# ioExpand.net
KiCad netlist of a schematic drawn in EAGLE
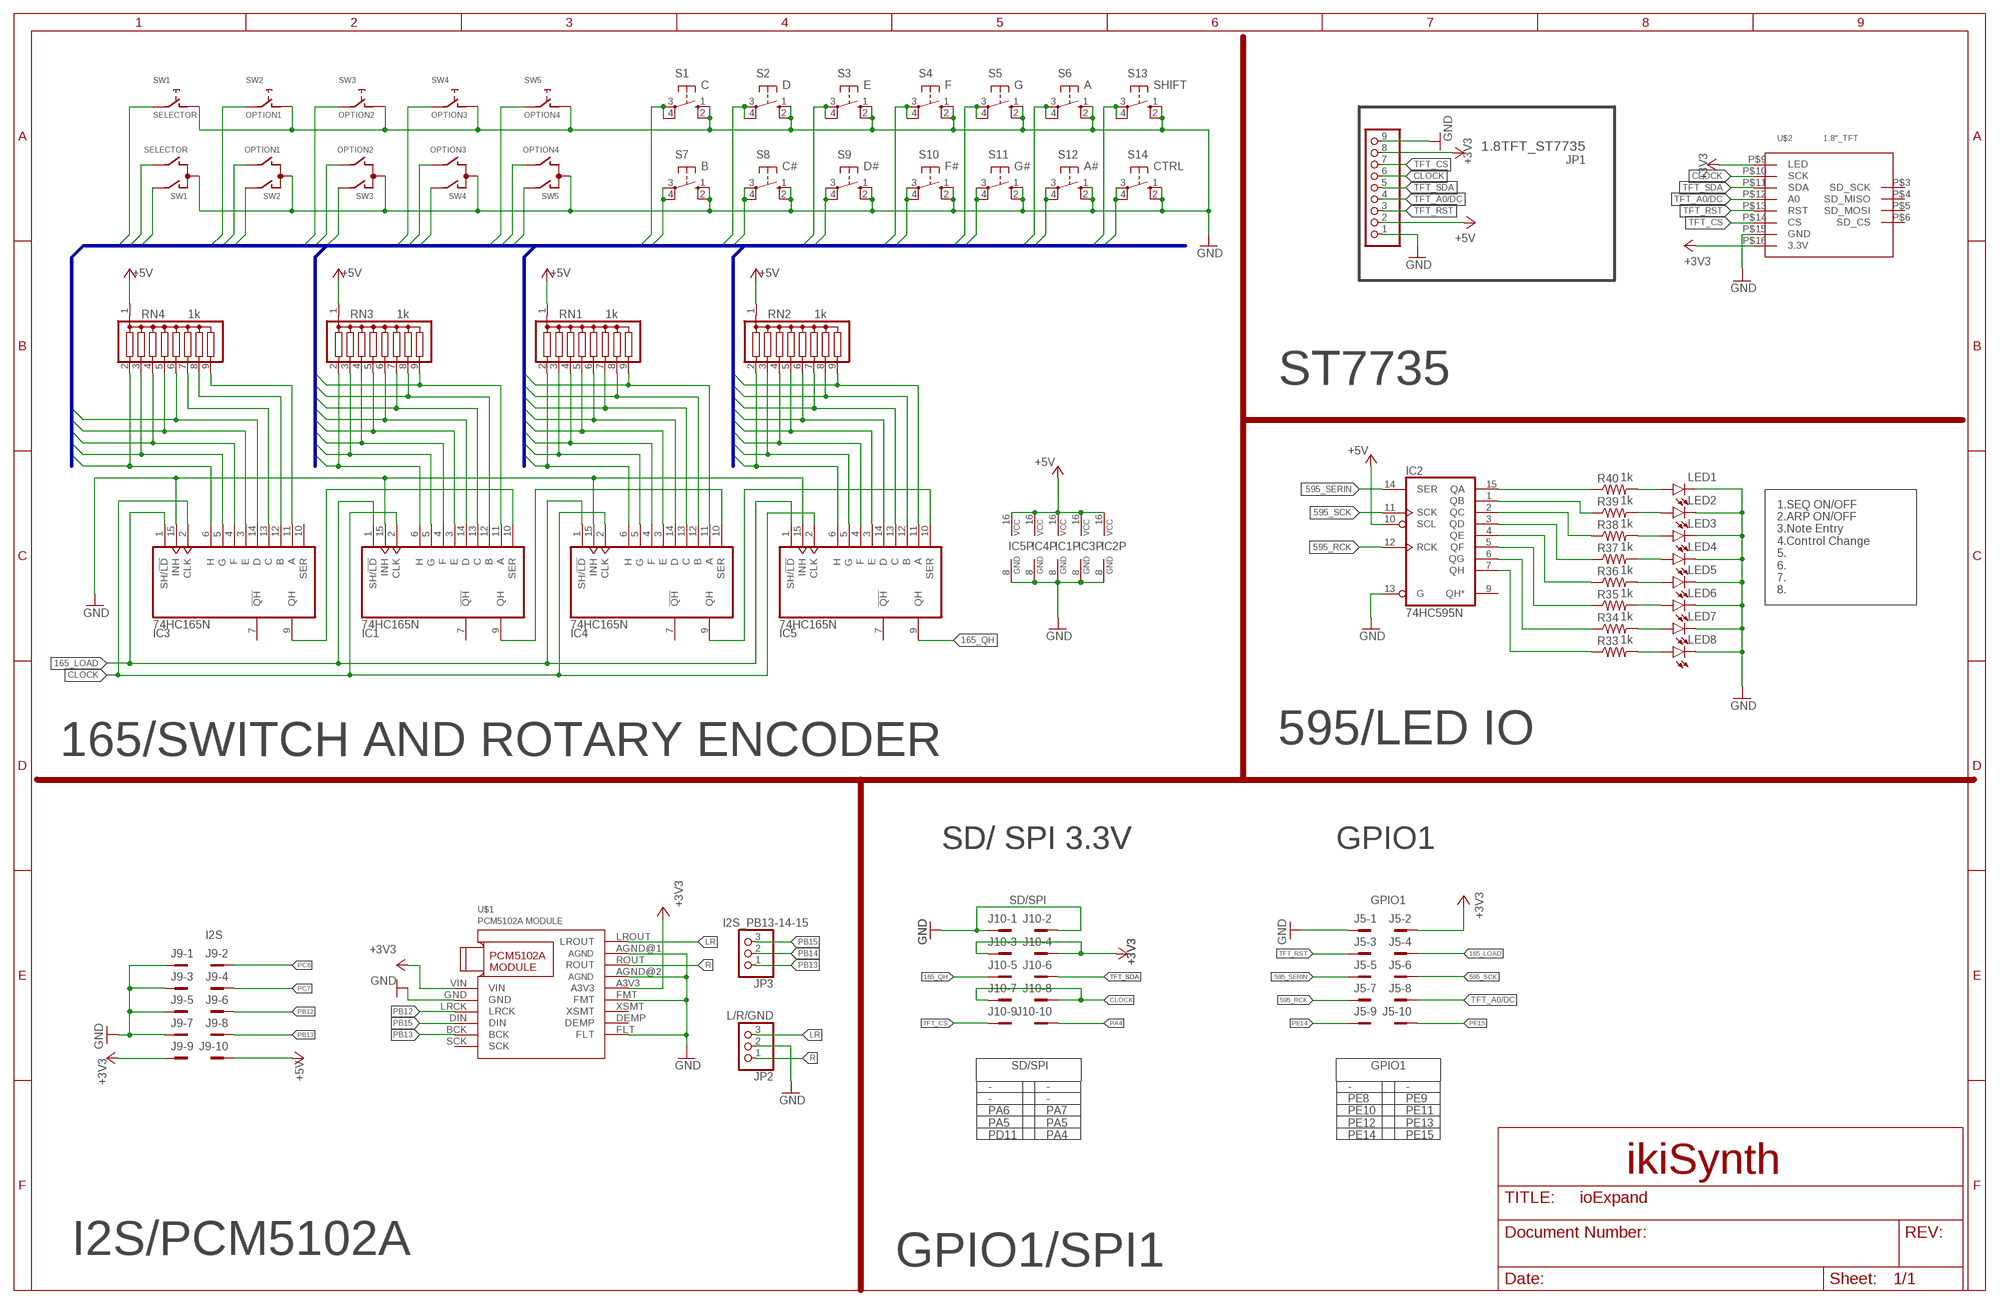
[diagram p0: schematic, sheet 1]

(export (version "E")
  (design (tool "Eeschema 10.0.6"))
  (components
    (comp (ref "IC1")
      (value "74HC165N")
      (footprint "eagle-import:DIL16")
      (libsource (lib "eagle-import") (part "74165NHC"))
    )
    (comp (ref "IC2")
      (value "74HC595N")
      (footprint "eagle-import:DIL16")
      (libsource (lib "eagle-import") (part "74595NHC"))
    )
    (comp (ref "IC3")
      (value "74HC165N")
      (footprint "eagle-import:DIL16")
      (libsource (lib "eagle-import") (part "74165NHC"))
    )
    (comp (ref "IC4")
      (value "74HC165N")
      (footprint "eagle-import:DIL16")
      (libsource (lib "eagle-import") (part "74165NHC"))
    )
    (comp (ref "IC5")
      (value "74HC165N")
      (footprint "eagle-import:DIL16")
      (libsource (lib "eagle-import") (part "74165NHC"))
    )
    (comp (ref "J5")
      (value "GPIO1")
      (footprint "eagle-import:PAK100_2500-10")
      (fields (field (name "MF") "3M") (field (name "MPN") "2510-6002UB"))
      (libsource (lib "eagle-import") (part "2510-"))
    )
    (comp (ref "J9")
      (value "I2S")
      (footprint "eagle-import:PAK100_2500-10")
      (fields (field (name "MF") "3M") (field (name "MPN") "2510-6002UB"))
      (libsource (lib "eagle-import") (part "2510-"))
    )
    (comp (ref "J10")
      (value "SD/SPI")
      (footprint "eagle-import:PAK100_2500-10")
      (fields (field (name "MF") "3M") (field (name "MPN") "2510-6002UB"))
      (libsource (lib "eagle-import") (part "2510-"))
    )
    (comp (ref "JP1")
      (value "1.8TFT_ST7735")
      (footprint "eagle-import:1X09")
      (libsource (lib "eagle-import") (part "PINHD-1X9"))
    )
    (comp (ref "JP2")
      (value "L/R/GND")
      (footprint "eagle-import:1X03")
      (libsource (lib "eagle-import") (part "PINHD-1X3"))
    )
    (comp (ref "JP3")
      (value "I2S_PB13-14-15")
      (footprint "eagle-import:1X03")
      (libsource (lib "eagle-import") (part "PINHD-1X3"))
    )
    (comp (ref "LED1")
      (value "LED3MM")
      (footprint "eagle-import:LED3MM")
      (libsource (lib "eagle-import") (part "LED3MM"))
    )
    (comp (ref "LED2")
      (value "LED3MM")
      (footprint "eagle-import:LED3MM")
      (libsource (lib "eagle-import") (part "LED3MM"))
    )
    (comp (ref "LED3")
      (value "LED3MM")
      (footprint "eagle-import:LED3MM")
      (libsource (lib "eagle-import") (part "LED3MM"))
    )
    (comp (ref "LED4")
      (value "LED3MM")
      (footprint "eagle-import:LED3MM")
      (libsource (lib "eagle-import") (part "LED3MM"))
    )
    (comp (ref "LED5")
      (value "LED3MM")
      (footprint "eagle-import:LED3MM")
      (libsource (lib "eagle-import") (part "LED3MM"))
    )
    (comp (ref "LED6")
      (value "LED3MM")
      (footprint "eagle-import:LED3MM")
      (libsource (lib "eagle-import") (part "LED3MM"))
    )
    (comp (ref "LED7")
      (value "LED3MM")
      (footprint "eagle-import:LED3MM")
      (libsource (lib "eagle-import") (part "LED3MM"))
    )
    (comp (ref "LED8")
      (value "LED3MM")
      (footprint "eagle-import:LED3MM")
      (libsource (lib "eagle-import") (part "LED3MM"))
    )
    (comp (ref "R33")
      (value "1k")
      (footprint "eagle-import:M1206")
      (libsource (lib "eagle-import") (part "R-US_M1206"))
    )
    (comp (ref "R34")
      (value "1k")
      (footprint "eagle-import:M1206")
      (libsource (lib "eagle-import") (part "R-US_M1206"))
    )
    (comp (ref "R35")
      (value "1k")
      (footprint "eagle-import:M1206")
      (libsource (lib "eagle-import") (part "R-US_M1206"))
    )
    (comp (ref "R36")
      (value "1k")
      (footprint "eagle-import:M1206")
      (libsource (lib "eagle-import") (part "R-US_M1206"))
    )
    (comp (ref "R37")
      (value "1k")
      (footprint "eagle-import:M1206")
      (libsource (lib "eagle-import") (part "R-US_M1206"))
    )
    (comp (ref "R38")
      (value "1k")
      (footprint "eagle-import:M1206")
      (libsource (lib "eagle-import") (part "R-US_M1206"))
    )
    (comp (ref "R39")
      (value "1k")
      (footprint "eagle-import:M1206")
      (libsource (lib "eagle-import") (part "R-US_M1206"))
    )
    (comp (ref "R40")
      (value "1k")
      (footprint "eagle-import:M1206")
      (libsource (lib "eagle-import") (part "R-US_M1206"))
    )
    (comp (ref "RN1")
      (value "1k")
      (footprint "eagle-import:SIL9")
      (libsource (lib "eagle-import") (part "G08R"))
    )
    (comp (ref "RN2")
      (value "1k")
      (footprint "eagle-import:SIL9")
      (libsource (lib "eagle-import") (part "G08R"))
    )
    (comp (ref "RN3")
      (value "1k")
      (footprint "eagle-import:SIL9")
      (libsource (lib "eagle-import") (part "G08R"))
    )
    (comp (ref "RN4")
      (value "1k")
      (footprint "eagle-import:SIL9")
      (libsource (lib "eagle-import") (part "G08R"))
    )
    (comp (ref "S1")
      (value "C")
      (footprint "eagle-import:B3F-40XX")
      (fields (field (name "MF") "OMRON COMPONENTS USA") (field (name "MPN") "B3F-4000"))
      (libsource (lib "eagle-import") (part "40-XX"))
    )
    (comp (ref "S2")
      (value "D")
      (footprint "eagle-import:B3F-40XX")
      (fields (field (name "MF") "OMRON COMPONENTS USA") (field (name "MPN") "B3F-4000"))
      (libsource (lib "eagle-import") (part "40-XX"))
    )
    (comp (ref "S3")
      (value "E")
      (footprint "eagle-import:B3F-40XX")
      (fields (field (name "MF") "OMRON COMPONENTS USA") (field (name "MPN") "B3F-4000"))
      (libsource (lib "eagle-import") (part "40-XX"))
    )
    (comp (ref "S4")
      (value "F")
      (footprint "eagle-import:B3F-40XX")
      (fields (field (name "MF") "OMRON COMPONENTS USA") (field (name "MPN") "B3F-4000"))
      (libsource (lib "eagle-import") (part "40-XX"))
    )
    (comp (ref "S5")
      (value "G")
      (footprint "eagle-import:B3F-40XX")
      (fields (field (name "MF") "OMRON COMPONENTS USA") (field (name "MPN") "B3F-4000"))
      (libsource (lib "eagle-import") (part "40-XX"))
    )
    (comp (ref "S6")
      (value "A")
      (footprint "eagle-import:B3F-40XX")
      (fields (field (name "MF") "OMRON COMPONENTS USA") (field (name "MPN") "B3F-4000"))
      (libsource (lib "eagle-import") (part "40-XX"))
    )
    (comp (ref "S7")
      (value "B")
      (footprint "eagle-import:B3F-40XX")
      (fields (field (name "MF") "OMRON COMPONENTS USA") (field (name "MPN") "B3F-4000"))
      (libsource (lib "eagle-import") (part "40-XX"))
    )
    (comp (ref "S8")
      (value "C#")
      (footprint "eagle-import:B3F-40XX")
      (fields (field (name "MF") "OMRON COMPONENTS USA") (field (name "MPN") "B3F-4000"))
      (libsource (lib "eagle-import") (part "40-XX"))
    )
    (comp (ref "S9")
      (value "D#")
      (footprint "eagle-import:B3F-40XX")
      (fields (field (name "MF") "OMRON COMPONENTS USA") (field (name "MPN") "B3F-4000"))
      (libsource (lib "eagle-import") (part "40-XX"))
    )
    (comp (ref "S10")
      (value "F#")
      (footprint "eagle-import:B3F-40XX")
      (fields (field (name "MF") "OMRON COMPONENTS USA") (field (name "MPN") "B3F-4000"))
      (libsource (lib "eagle-import") (part "40-XX"))
    )
    (comp (ref "S11")
      (value "G#")
      (footprint "eagle-import:B3F-40XX")
      (fields (field (name "MF") "OMRON COMPONENTS USA") (field (name "MPN") "B3F-4000"))
      (libsource (lib "eagle-import") (part "40-XX"))
    )
    (comp (ref "S12")
      (value "A#")
      (footprint "eagle-import:B3F-40XX")
      (fields (field (name "MF") "OMRON COMPONENTS USA") (field (name "MPN") "B3F-4000"))
      (libsource (lib "eagle-import") (part "40-XX"))
    )
    (comp (ref "S13")
      (value "SHIFT")
      (footprint "eagle-import:B3F-40XX")
      (fields (field (name "MF") "OMRON COMPONENTS USA") (field (name "MPN") "B3F-4000"))
      (libsource (lib "eagle-import") (part "40-XX"))
    )
    (comp (ref "S14")
      (value "CTRL")
      (footprint "eagle-import:B3F-40XX")
      (fields (field (name "MF") "OMRON COMPONENTS USA") (field (name "MPN") "B3F-4000"))
      (libsource (lib "eagle-import") (part "40-XX"))
    )
    (comp (ref "SW1")
      (value "SELECTOR")
      (footprint "eagle-import:ALPS_EC12E_SW")
      (fields (field (name "MPN") "EC12E2424407"))
      (libsource (lib "eagle-import") (part "EC12E_SW"))
    )
    (comp (ref "SW2")
      (value "OPTION1")
      (footprint "eagle-import:ALPS_EC12E_SW")
      (fields (field (name "MPN") "EC12E2424407"))
      (libsource (lib "eagle-import") (part "EC12E_SW"))
    )
    (comp (ref "SW3")
      (value "OPTION2")
      (footprint "eagle-import:ALPS_EC12E_SW")
      (fields (field (name "MPN") "EC12E2424407"))
      (libsource (lib "eagle-import") (part "EC12E_SW"))
    )
    (comp (ref "SW4")
      (value "OPTION3")
      (footprint "eagle-import:ALPS_EC12E_SW")
      (fields (field (name "MPN") "EC12E2424407"))
      (libsource (lib "eagle-import") (part "EC12E_SW"))
    )
    (comp (ref "SW5")
      (value "OPTION4")
      (footprint "eagle-import:ALPS_EC12E_SW")
      (fields (field (name "MPN") "EC12E2424407"))
      (libsource (lib "eagle-import") (part "EC12E_SW"))
    )
    (comp (ref "U$1")
      (value "PCM5102A_MODULE")
      (footprint "eagle-import:PCM5102A_MODULE")
      (libsource (lib "eagle-import") (part "PCM5102A_MODULE"))
    )
    (comp (ref "U$2")
      (value "1.8\"_TFT")
      (footprint "eagle-import:1.8__TFT")
      (libsource (lib "eagle-import") (part "1.8{dblquote}_TFT"))
    )
  )
  (nets
    (net (code "1") (name "+3V3") (class "Default")
      (node (ref "J10") (pin "3") (pinfunction "KL_3") (pintype "passive"))
      (node (ref "J10") (pin "4") (pinfunction "KL_4") (pintype "passive"))
      (node (ref "J5") (pin "2") (pinfunction "KL_2") (pintype "passive"))
      (node (ref "J9") (pin "9") (pinfunction "KL_9") (pintype "passive"))
      (node (ref "JP1") (pin "8") (pinfunction "8_8") (pintype "passive"))
      (node (ref "U$1") (pin "A3V3") (pinfunction "A3V3_A3V3") (pintype "power_in"))
      (node (ref "U$1") (pin "VIN") (pinfunction "VIN_VIN") (pintype "power_in"))
      (node (ref "U$2") (pin "P$16") (pinfunction "3.3V_P$16") (pintype "bidirectional"))
      (node (ref "U$2") (pin "P$9") (pinfunction "LED_P$9") (pintype "bidirectional"))
    )
    (net (code "2") (name "+5V") (class "Default")
      (node (ref "IC1") (pin "16") (pinfunction "VCC_16") (pintype "power_in"))
      (node (ref "IC2") (pin "10") (pinfunction "SCL_10") (pintype "input"))
      (node (ref "IC2") (pin "16") (pinfunction "VCC_16") (pintype "power_in"))
      (node (ref "IC3") (pin "16") (pinfunction "VCC_16") (pintype "power_in"))
      (node (ref "IC4") (pin "16") (pinfunction "VCC_16") (pintype "power_in"))
      (node (ref "IC5") (pin "16") (pinfunction "VCC_16") (pintype "power_in"))
      (node (ref "J9") (pin "10") (pinfunction "KL_10") (pintype "passive"))
      (node (ref "JP1") (pin "2") (pinfunction "2_2") (pintype "passive"))
      (node (ref "RN1") (pin "1") (pinfunction "1_1") (pintype "passive"))
      (node (ref "RN2") (pin "1") (pinfunction "1_1") (pintype "passive"))
      (node (ref "RN3") (pin "1") (pinfunction "1_1") (pintype "passive"))
      (node (ref "RN4") (pin "1") (pinfunction "1_1") (pintype "passive"))
    )
    (net (code "3") (name "/CTRL") (class "Default")
      (node (ref "IC3") (pin "3") (pinfunction "E_3") (pintype "input"))
      (node (ref "RN4") (pin "5") (pinfunction "5_5") (pintype "passive"))
      (node (ref "S14") (pin "3") (pinfunction "P_3") (pintype "passive"))
      (node (ref "S14") (pin "4") (pinfunction "P1_4") (pintype "passive"))
    )
    (net (code "4") (name "/KEY1") (class "Default")
      (node (ref "IC1") (pin "11") (pinfunction "A_11") (pintype "input"))
      (node (ref "RN3") (pin "9") (pinfunction "9_9") (pintype "passive"))
      (node (ref "S1") (pin "3") (pinfunction "P_3") (pintype "passive"))
      (node (ref "S1") (pin "4") (pinfunction "P1_4") (pintype "passive"))
    )
    (net (code "5") (name "/KEY2") (class "Default")
      (node (ref "IC1") (pin "13") (pinfunction "C_13") (pintype "input"))
      (node (ref "RN3") (pin "7") (pinfunction "7_7") (pintype "passive"))
      (node (ref "S2") (pin "3") (pinfunction "P_3") (pintype "passive"))
      (node (ref "S2") (pin "4") (pinfunction "P1_4") (pintype "passive"))
    )
    (net (code "6") (name "/KEY3") (class "Default")
      (node (ref "IC1") (pin "3") (pinfunction "E_3") (pintype "input"))
      (node (ref "RN3") (pin "5") (pinfunction "5_5") (pintype "passive"))
      (node (ref "S3") (pin "3") (pinfunction "P_3") (pintype "passive"))
      (node (ref "S3") (pin "4") (pinfunction "P1_4") (pintype "passive"))
    )
    (net (code "7") (name "/KEY4") (class "Default")
      (node (ref "IC1") (pin "4") (pinfunction "F_4") (pintype "input"))
      (node (ref "RN3") (pin "4") (pinfunction "4_4") (pintype "passive"))
      (node (ref "S4") (pin "3") (pinfunction "P_3") (pintype "passive"))
      (node (ref "S4") (pin "4") (pinfunction "P1_4") (pintype "passive"))
    )
    (net (code "8") (name "/KEY5") (class "Default")
      (node (ref "IC4") (pin "11") (pinfunction "A_11") (pintype "input"))
      (node (ref "RN1") (pin "9") (pinfunction "9_9") (pintype "passive"))
      (node (ref "S5") (pin "3") (pinfunction "P_3") (pintype "passive"))
      (node (ref "S5") (pin "4") (pinfunction "P1_4") (pintype "passive"))
    )
    (net (code "9") (name "/KEY6") (class "Default")
      (node (ref "IC4") (pin "12") (pinfunction "B_12") (pintype "input"))
      (node (ref "RN1") (pin "8") (pinfunction "8_8") (pintype "passive"))
      (node (ref "S6") (pin "3") (pinfunction "P_3") (pintype "passive"))
      (node (ref "S6") (pin "4") (pinfunction "P1_4") (pintype "passive"))
    )
    (net (code "10") (name "/KEY7") (class "Default")
      (node (ref "IC4") (pin "14") (pinfunction "D_14") (pintype "input"))
      (node (ref "RN1") (pin "6") (pinfunction "6_6") (pintype "passive"))
      (node (ref "S7") (pin "3") (pinfunction "P_3") (pintype "passive"))
      (node (ref "S7") (pin "4") (pinfunction "P1_4") (pintype "passive"))
    )
    (net (code "11") (name "/KEY8") (class "Default")
      (node (ref "IC1") (pin "12") (pinfunction "B_12") (pintype "input"))
      (node (ref "RN3") (pin "8") (pinfunction "8_8") (pintype "passive"))
      (node (ref "S8") (pin "3") (pinfunction "P_3") (pintype "passive"))
      (node (ref "S8") (pin "4") (pinfunction "P1_4") (pintype "passive"))
    )
    (net (code "12") (name "/KEY9") (class "Default")
      (node (ref "IC1") (pin "14") (pinfunction "D_14") (pintype "input"))
      (node (ref "RN3") (pin "6") (pinfunction "6_6") (pintype "passive"))
      (node (ref "S9") (pin "3") (pinfunction "P_3") (pintype "passive"))
      (node (ref "S9") (pin "4") (pinfunction "P1_4") (pintype "passive"))
    )
    (net (code "13") (name "/KEY10") (class "Default")
      (node (ref "IC1") (pin "5") (pinfunction "G_5") (pintype "input"))
      (node (ref "RN3") (pin "3") (pinfunction "3_3") (pintype "passive"))
      (node (ref "S10") (pin "3") (pinfunction "P_3") (pintype "passive"))
      (node (ref "S10") (pin "4") (pinfunction "P1_4") (pintype "passive"))
    )
    (net (code "14") (name "/KEY11") (class "Default")
      (node (ref "IC1") (pin "6") (pinfunction "H_6") (pintype "input"))
      (node (ref "RN3") (pin "2") (pinfunction "2_2") (pintype "passive"))
      (node (ref "S11") (pin "3") (pinfunction "P_3") (pintype "passive"))
      (node (ref "S11") (pin "4") (pinfunction "P1_4") (pintype "passive"))
    )
    (net (code "15") (name "/KEY12") (class "Default")
      (node (ref "IC4") (pin "13") (pinfunction "C_13") (pintype "input"))
      (node (ref "RN1") (pin "7") (pinfunction "7_7") (pintype "passive"))
      (node (ref "S12") (pin "3") (pinfunction "P_3") (pintype "passive"))
      (node (ref "S12") (pin "4") (pinfunction "P1_4") (pintype "passive"))
    )
    (net (code "16") (name "/ROTSW1") (class "Default")
      (node (ref "IC3") (pin "6") (pinfunction "H_6") (pintype "input"))
      (node (ref "RN4") (pin "2") (pinfunction "2_2") (pintype "passive"))
      (node (ref "SW1") (pin "E") (pinfunction "2_E") (pintype "passive"))
    )
    (net (code "17") (name "/ROTSW2") (class "Default")
      (node (ref "IC5") (pin "6") (pinfunction "H_6") (pintype "input"))
      (node (ref "RN2") (pin "2") (pinfunction "2_2") (pintype "passive"))
      (node (ref "SW2") (pin "E") (pinfunction "2_E") (pintype "passive"))
    )
    (net (code "18") (name "/ROTSW3") (class "Default")
      (node (ref "IC5") (pin "3") (pinfunction "E_3") (pintype "input"))
      (node (ref "RN2") (pin "5") (pinfunction "5_5") (pintype "passive"))
      (node (ref "SW3") (pin "E") (pinfunction "2_E") (pintype "passive"))
    )
    (net (code "19") (name "/ROTSW4") (class "Default")
      (node (ref "IC5") (pin "12") (pinfunction "B_12") (pintype "input"))
      (node (ref "RN2") (pin "8") (pinfunction "8_8") (pintype "passive"))
      (node (ref "SW4") (pin "E") (pinfunction "2_E") (pintype "passive"))
    )
    (net (code "20") (name "/ROTSW5") (class "Default")
      (node (ref "IC4") (pin "5") (pinfunction "G_5") (pintype "input"))
      (node (ref "RN1") (pin "3") (pinfunction "3_3") (pintype "passive"))
      (node (ref "SW5") (pin "E") (pinfunction "2_E") (pintype "passive"))
    )
    (net (code "21") (name "/ROTSW_AB1") (class "Default")
      (node (ref "IC3") (pin "5") (pinfunction "G_5") (pintype "input"))
      (node (ref "RN4") (pin "3") (pinfunction "3_3") (pintype "passive"))
      (node (ref "SW1") (pin "B") (pinfunction "B_B") (pintype "passive"))
    )
    (net (code "22") (name "/ROTSW_AB2") (class "Default")
      (node (ref "IC3") (pin "4") (pinfunction "F_4") (pintype "input"))
      (node (ref "RN4") (pin "4") (pinfunction "4_4") (pintype "passive"))
      (node (ref "SW1") (pin "A") (pinfunction "A_A") (pintype "passive"))
    )
    (net (code "23") (name "/ROTSW_AB3") (class "Default")
      (node (ref "IC5") (pin "5") (pinfunction "G_5") (pintype "input"))
      (node (ref "RN2") (pin "3") (pinfunction "3_3") (pintype "passive"))
      (node (ref "SW2") (pin "B") (pinfunction "B_B") (pintype "passive"))
    )
    (net (code "24") (name "/ROTSW_AB4") (class "Default")
      (node (ref "IC5") (pin "4") (pinfunction "F_4") (pintype "input"))
      (node (ref "RN2") (pin "4") (pinfunction "4_4") (pintype "passive"))
      (node (ref "SW2") (pin "A") (pinfunction "A_A") (pintype "passive"))
    )
    (net (code "25") (name "/ROTSW_AB5") (class "Default")
      (node (ref "IC5") (pin "14") (pinfunction "D_14") (pintype "input"))
      (node (ref "RN2") (pin "6") (pinfunction "6_6") (pintype "passive"))
      (node (ref "SW3") (pin "B") (pinfunction "B_B") (pintype "passive"))
    )
    (net (code "26") (name "/ROTSW_AB6") (class "Default")
      (node (ref "IC5") (pin "13") (pinfunction "C_13") (pintype "input"))
      (node (ref "RN2") (pin "7") (pinfunction "7_7") (pintype "passive"))
      (node (ref "SW3") (pin "A") (pinfunction "A_A") (pintype "passive"))
    )
    (net (code "27") (name "/ROTSW_AB7") (class "Default")
      (node (ref "IC5") (pin "11") (pinfunction "A_11") (pintype "input"))
      (node (ref "RN2") (pin "9") (pinfunction "9_9") (pintype "passive"))
      (node (ref "SW4") (pin "B") (pinfunction "B_B") (pintype "passive"))
    )
    (net (code "28") (name "/ROTSW_AB8") (class "Default")
      (node (ref "IC4") (pin "6") (pinfunction "H_6") (pintype "input"))
      (node (ref "RN1") (pin "2") (pinfunction "2_2") (pintype "passive"))
      (node (ref "SW4") (pin "A") (pinfunction "A_A") (pintype "passive"))
    )
    (net (code "29") (name "/ROTSW_AB9") (class "Default")
      (node (ref "IC4") (pin "4") (pinfunction "F_4") (pintype "input"))
      (node (ref "RN1") (pin "4") (pinfunction "4_4") (pintype "passive"))
      (node (ref "SW5") (pin "B") (pinfunction "B_B") (pintype "passive"))
    )
    (net (code "30") (name "/ROTSW_AB10") (class "Default")
      (node (ref "IC4") (pin "3") (pinfunction "E_3") (pintype "input"))
      (node (ref "RN1") (pin "5") (pinfunction "5_5") (pintype "passive"))
      (node (ref "SW5") (pin "A") (pinfunction "A_A") (pintype "passive"))
    )
    (net (code "31") (name "/SHIFT") (class "Default")
      (node (ref "IC3") (pin "14") (pinfunction "D_14") (pintype "input"))
      (node (ref "RN4") (pin "6") (pinfunction "6_6") (pintype "passive"))
      (node (ref "S13") (pin "3") (pinfunction "P_3") (pintype "passive"))
      (node (ref "S13") (pin "4") (pinfunction "P1_4") (pintype "passive"))
    )
    (net (code "32") (name "165_LOAD") (class "Default")
      (node (ref "IC1") (pin "1") (pinfunction "SH/~{LD}_1") (pintype "input"))
      (node (ref "IC3") (pin "1") (pinfunction "SH/~{LD}_1") (pintype "input"))
      (node (ref "IC4") (pin "1") (pinfunction "SH/~{LD}_1") (pintype "input"))
      (node (ref "IC5") (pin "1") (pinfunction "SH/~{LD}_1") (pintype "input"))
      (node (ref "J5") (pin "4") (pinfunction "KL_4") (pintype "passive"))
    )
    (net (code "33") (name "165_QH") (class "Default")
      (node (ref "IC5") (pin "9") (pinfunction "QH_9") (pintype "output"))
      (node (ref "J10") (pin "5") (pinfunction "KL_5") (pintype "passive"))
    )
    (net (code "34") (name "595_RCK") (class "Default")
      (node (ref "IC2") (pin "12") (pinfunction "RCK_12") (pintype "input"))
      (node (ref "J5") (pin "7") (pinfunction "KL_7") (pintype "passive"))
    )
    (net (code "35") (name "595_SCK") (class "Default")
      (node (ref "IC2") (pin "11") (pinfunction "SCK_11") (pintype "input"))
      (node (ref "J5") (pin "6") (pinfunction "KL_6") (pintype "passive"))
    )
    (net (code "36") (name "595_SERIN") (class "Default")
      (node (ref "IC2") (pin "14") (pinfunction "SER_14") (pintype "input"))
      (node (ref "J5") (pin "5") (pinfunction "KL_5") (pintype "passive"))
    )
    (net (code "37") (name "CLOCK") (class "Default")
      (node (ref "IC1") (pin "2") (pinfunction "CLK_2") (pintype "input"))
      (node (ref "IC3") (pin "2") (pinfunction "CLK_2") (pintype "input"))
      (node (ref "IC4") (pin "2") (pinfunction "CLK_2") (pintype "input"))
      (node (ref "IC5") (pin "2") (pinfunction "CLK_2") (pintype "input"))
      (node (ref "J10") (pin "7") (pinfunction "KL_7") (pintype "passive"))
      (node (ref "J10") (pin "8") (pinfunction "KL_8") (pintype "passive"))
      (node (ref "JP1") (pin "6") (pinfunction "6_6") (pintype "passive"))
      (node (ref "U$2") (pin "P$10") (pinfunction "SCK_P$10") (pintype "bidirectional"))
    )
    (net (code "38") (name "GND") (class "Default")
      (node (ref "IC1") (pin "15") (pinfunction "INH_15") (pintype "input"))
      (node (ref "IC1") (pin "8") (pinfunction "GND_8") (pintype "power_in"))
      (node (ref "IC2") (pin "13") (pinfunction "G_13") (pintype "input"))
      (node (ref "IC2") (pin "8") (pinfunction "GND_8") (pintype "power_in"))
      (node (ref "IC3") (pin "15") (pinfunction "INH_15") (pintype "input"))
      (node (ref "IC3") (pin "8") (pinfunction "GND_8") (pintype "power_in"))
      (node (ref "IC4") (pin "15") (pinfunction "INH_15") (pintype "input"))
      (node (ref "IC4") (pin "8") (pinfunction "GND_8") (pintype "power_in"))
      (node (ref "IC5") (pin "15") (pinfunction "INH_15") (pintype "input"))
      (node (ref "IC5") (pin "8") (pinfunction "GND_8") (pintype "power_in"))
      (node (ref "J10") (pin "1") (pinfunction "KL_1") (pintype "passive"))
      (node (ref "J10") (pin "2") (pinfunction "KL_2") (pintype "passive"))
      (node (ref "J5") (pin "1") (pinfunction "KL_1") (pintype "passive"))
      (node (ref "J9") (pin "1") (pinfunction "KL_1") (pintype "passive"))
      (node (ref "J9") (pin "3") (pinfunction "KL_3") (pintype "passive"))
      (node (ref "J9") (pin "5") (pinfunction "KL_5") (pintype "passive"))
      (node (ref "J9") (pin "7") (pinfunction "KL_7") (pintype "passive"))
      (node (ref "JP1") (pin "1") (pinfunction "1_1") (pintype "passive"))
      (node (ref "JP1") (pin "9") (pinfunction "9_9") (pintype "passive"))
      (node (ref "JP2") (pin "2") (pinfunction "2_2") (pintype "passive"))
      (node (ref "LED1") (pin "K") (pinfunction "C_K") (pintype "passive"))
      (node (ref "LED2") (pin "K") (pinfunction "C_K") (pintype "passive"))
      (node (ref "LED3") (pin "K") (pinfunction "C_K") (pintype "passive"))
      (node (ref "LED4") (pin "K") (pinfunction "C_K") (pintype "passive"))
      (node (ref "LED5") (pin "K") (pinfunction "C_K") (pintype "passive"))
      (node (ref "LED6") (pin "K") (pinfunction "C_K") (pintype "passive"))
      (node (ref "LED7") (pin "K") (pinfunction "C_K") (pintype "passive"))
      (node (ref "LED8") (pin "K") (pinfunction "C_K") (pintype "passive"))
      (node (ref "S1") (pin "1") (pinfunction "S_1") (pintype "passive"))
      (node (ref "S1") (pin "2") (pinfunction "S1_2") (pintype "passive"))
      (node (ref "S10") (pin "1") (pinfunction "S_1") (pintype "passive"))
      (node (ref "S10") (pin "2") (pinfunction "S1_2") (pintype "passive"))
      (node (ref "S11") (pin "1") (pinfunction "S_1") (pintype "passive"))
      (node (ref "S11") (pin "2") (pinfunction "S1_2") (pintype "passive"))
      (node (ref "S12") (pin "1") (pinfunction "S_1") (pintype "passive"))
      (node (ref "S12") (pin "2") (pinfunction "S1_2") (pintype "passive"))
      (node (ref "S13") (pin "1") (pinfunction "S_1") (pintype "passive"))
      (node (ref "S13") (pin "2") (pinfunction "S1_2") (pintype "passive"))
      (node (ref "S14") (pin "1") (pinfunction "S_1") (pintype "passive"))
      (node (ref "S14") (pin "2") (pinfunction "S1_2") (pintype "passive"))
      (node (ref "S2") (pin "1") (pinfunction "S_1") (pintype "passive"))
      (node (ref "S2") (pin "2") (pinfunction "S1_2") (pintype "passive"))
      (node (ref "S3") (pin "1") (pinfunction "S_1") (pintype "passive"))
      (node (ref "S3") (pin "2") (pinfunction "S1_2") (pintype "passive"))
      (node (ref "S4") (pin "1") (pinfunction "S_1") (pintype "passive"))
      (node (ref "S4") (pin "2") (pinfunction "S1_2") (pintype "passive"))
      (node (ref "S5") (pin "1") (pinfunction "S_1") (pintype "passive"))
      (node (ref "S5") (pin "2") (pinfunction "S1_2") (pintype "passive"))
      (node (ref "S6") (pin "1") (pinfunction "S_1") (pintype "passive"))
      (node (ref "S6") (pin "2") (pinfunction "S1_2") (pintype "passive"))
      (node (ref "S7") (pin "1") (pinfunction "S_1") (pintype "passive"))
      (node (ref "S7") (pin "2") (pinfunction "S1_2") (pintype "passive"))
      (node (ref "S8") (pin "1") (pinfunction "S_1") (pintype "passive"))
      (node (ref "S8") (pin "2") (pinfunction "S1_2") (pintype "passive"))
      (node (ref "S9") (pin "1") (pinfunction "S_1") (pintype "passive"))
      (node (ref "S9") (pin "2") (pinfunction "S1_2") (pintype "passive"))
      (node (ref "SW1") (pin "C") (pinfunction "C_C") (pintype "passive"))
      (node (ref "SW1") (pin "D") (pinfunction "1_D") (pintype "passive"))
      (node (ref "SW2") (pin "C") (pinfunction "C_C") (pintype "passive"))
      (node (ref "SW2") (pin "D") (pinfunction "1_D") (pintype "passive"))
      (node (ref "SW3") (pin "C") (pinfunction "C_C") (pintype "passive"))
      (node (ref "SW3") (pin "D") (pinfunction "1_D") (pintype "passive"))
      (node (ref "SW4") (pin "C") (pinfunction "C_C") (pintype "passive"))
      (node (ref "SW4") (pin "D") (pinfunction "1_D") (pintype "passive"))
      (node (ref "SW5") (pin "C") (pinfunction "C_C") (pintype "passive"))
      (node (ref "SW5") (pin "D") (pinfunction "1_D") (pintype "passive"))
      (node (ref "U$1") (pin "AGND@1") (pinfunction "AGND_AGND@1") (pintype "power_in"))
      (node (ref "U$1") (pin "AGND@2") (pinfunction "AGND_AGND@2") (pintype "power_in"))
      (node (ref "U$1") (pin "FLT") (pinfunction "FLT_FLT") (pintype "input"))
      (node (ref "U$1") (pin "FMT") (pinfunction "FMT_FMT") (pintype "input"))
      (node (ref "U$1") (pin "GND") (pinfunction "GND_GND") (pintype "power_in"))
      (node (ref "U$2") (pin "P$15") (pinfunction "GND_P$15") (pintype "bidirectional"))
    )
    (net (code "39") (name "LR") (class "Default")
      (node (ref "JP2") (pin "3") (pinfunction "3_3") (pintype "passive"))
      (node (ref "U$1") (pin "LROUT") (pinfunction "LROUT_LROUT") (pintype "output"))
    )
    (net (code "40") (name "Net-(IC1A-QH)") (class "Default")
      (node (ref "IC1") (pin "9") (pinfunction "QH_9") (pintype "output"))
      (node (ref "IC4") (pin "10") (pinfunction "SER_10") (pintype "input"))
    )
    (net (code "41") (name "Net-(IC1A-SER)") (class "Default")
      (node (ref "IC1") (pin "10") (pinfunction "SER_10") (pintype "input"))
      (node (ref "IC3") (pin "9") (pinfunction "QH_9") (pintype "output"))
    )
    (net (code "42") (name "Net-(IC2A-QA)") (class "Default")
      (node (ref "IC2") (pin "15") (pinfunction "QA_15") (pintype "tri_state"))
      (node (ref "R40") (pin "1") (pinfunction "1_1") (pintype "passive"))
    )
    (net (code "43") (name "Net-(IC2A-QB)") (class "Default")
      (node (ref "IC2") (pin "1") (pinfunction "QB_1") (pintype "tri_state"))
      (node (ref "R39") (pin "1") (pinfunction "1_1") (pintype "passive"))
    )
    (net (code "44") (name "Net-(IC2A-QC)") (class "Default")
      (node (ref "IC2") (pin "2") (pinfunction "QC_2") (pintype "tri_state"))
      (node (ref "R38") (pin "1") (pinfunction "1_1") (pintype "passive"))
    )
    (net (code "45") (name "Net-(IC2A-QD)") (class "Default")
      (node (ref "IC2") (pin "3") (pinfunction "QD_3") (pintype "tri_state"))
      (node (ref "R37") (pin "1") (pinfunction "1_1") (pintype "passive"))
    )
    (net (code "46") (name "Net-(IC2A-QE)") (class "Default")
      (node (ref "IC2") (pin "4") (pinfunction "QE_4") (pintype "tri_state"))
      (node (ref "R36") (pin "1") (pinfunction "1_1") (pintype "passive"))
    )
    (net (code "47") (name "Net-(IC2A-QF)") (class "Default")
      (node (ref "IC2") (pin "5") (pinfunction "QF_5") (pintype "tri_state"))
      (node (ref "R35") (pin "1") (pinfunction "1_1") (pintype "passive"))
    )
    (net (code "48") (name "Net-(IC2A-QG)") (class "Default")
      (node (ref "IC2") (pin "6") (pinfunction "QG_6") (pintype "tri_state"))
      (node (ref "R34") (pin "1") (pinfunction "1_1") (pintype "passive"))
    )
    (net (code "49") (name "Net-(IC2A-QH)") (class "Default")
      (node (ref "IC2") (pin "7") (pinfunction "QH_7") (pintype "tri_state"))
      (node (ref "R33") (pin "1") (pinfunction "1_1") (pintype "passive"))
    )
    (net (code "50") (name "Net-(IC3A-A)") (class "Default")
      (node (ref "IC3") (pin "11") (pinfunction "A_11") (pintype "input"))
      (node (ref "RN4") (pin "9") (pinfunction "9_9") (pintype "passive"))
    )
    (net (code "51") (name "Net-(IC3A-B)") (class "Default")
      (node (ref "IC3") (pin "12") (pinfunction "B_12") (pintype "input"))
      (node (ref "RN4") (pin "8") (pinfunction "8_8") (pintype "passive"))
    )
    (net (code "52") (name "Net-(IC3A-C)") (class "Default")
      (node (ref "IC3") (pin "13") (pinfunction "C_13") (pintype "input"))
      (node (ref "RN4") (pin "7") (pinfunction "7_7") (pintype "passive"))
    )
    (net (code "53") (name "Net-(IC4A-QH)") (class "Default")
      (node (ref "IC4") (pin "9") (pinfunction "QH_9") (pintype "output"))
      (node (ref "IC5") (pin "10") (pinfunction "SER_10") (pintype "input"))
    )
    (net (code "54") (name "Net-(LED1-PadA)") (class "Default")
      (node (ref "LED1") (pin "A") (pinfunction "A_A") (pintype "passive"))
      (node (ref "R40") (pin "2") (pinfunction "2_2") (pintype "passive"))
    )
    (net (code "55") (name "Net-(LED2-PadA)") (class "Default")
      (node (ref "LED2") (pin "A") (pinfunction "A_A") (pintype "passive"))
      (node (ref "R39") (pin "2") (pinfunction "2_2") (pintype "passive"))
    )
    (net (code "56") (name "Net-(LED3-PadA)") (class "Default")
      (node (ref "LED3") (pin "A") (pinfunction "A_A") (pintype "passive"))
      (node (ref "R38") (pin "2") (pinfunction "2_2") (pintype "passive"))
    )
    (net (code "57") (name "Net-(LED4-PadA)") (class "Default")
      (node (ref "LED4") (pin "A") (pinfunction "A_A") (pintype "passive"))
      (node (ref "R37") (pin "2") (pinfunction "2_2") (pintype "passive"))
    )
    (net (code "58") (name "Net-(LED5-PadA)") (class "Default")
      (node (ref "LED5") (pin "A") (pinfunction "A_A") (pintype "passive"))
      (node (ref "R36") (pin "2") (pinfunction "2_2") (pintype "passive"))
    )
    (net (code "59") (name "Net-(LED6-PadA)") (class "Default")
      (node (ref "LED6") (pin "A") (pinfunction "A_A") (pintype "passive"))
      (node (ref "R35") (pin "2") (pinfunction "2_2") (pintype "passive"))
    )
    (net (code "60") (name "Net-(LED7-PadA)") (class "Default")
      (node (ref "LED7") (pin "A") (pinfunction "A_A") (pintype "passive"))
      (node (ref "R34") (pin "2") (pinfunction "2_2") (pintype "passive"))
    )
    (net (code "61") (name "Net-(LED8-PadA)") (class "Default")
      (node (ref "LED8") (pin "A") (pinfunction "A_A") (pintype "passive"))
      (node (ref "R33") (pin "2") (pinfunction "2_2") (pintype "passive"))
    )
    (net (code "62") (name "PA4") (class "Default")
      (node (ref "J10") (pin "10") (pinfunction "KL_10") (pintype "passive"))
    )
    (net (code "63") (name "PB12") (class "Default")
      (node (ref "J9") (pin "6") (pinfunction "KL_6") (pintype "passive"))
      (node (ref "U$1") (pin "LRCK") (pinfunction "LRCK_LRCK") (pintype "output"))
    )
    (net (code "64") (name "PB13") (class "Default")
      (node (ref "J9") (pin "8") (pinfunction "KL_8") (pintype "passive"))
      (node (ref "JP3") (pin "1") (pinfunction "1_1") (pintype "passive"))
      (node (ref "U$1") (pin "BCK") (pinfunction "BCK_BCK") (pintype "input"))
    )
    (net (code "65") (name "PB14") (class "Default")
      (node (ref "JP3") (pin "2") (pinfunction "2_2") (pintype "passive"))
    )
    (net (code "66") (name "PB15") (class "Default")
      (node (ref "JP3") (pin "3") (pinfunction "3_3") (pintype "passive"))
      (node (ref "U$1") (pin "DIN") (pinfunction "DIN_DIN") (pintype "input"))
    )
    (net (code "67") (name "PC6") (class "Default")
      (node (ref "J9") (pin "2") (pinfunction "KL_2") (pintype "passive"))
    )
    (net (code "68") (name "PC7") (class "Default")
      (node (ref "J9") (pin "4") (pinfunction "KL_4") (pintype "passive"))
    )
    (net (code "69") (name "PE14") (class "Default")
      (node (ref "J5") (pin "9") (pinfunction "KL_9") (pintype "passive"))
    )
    (net (code "70") (name "PE15") (class "Default")
      (node (ref "J5") (pin "10") (pinfunction "KL_10") (pintype "passive"))
    )
    (net (code "71") (name "R") (class "Default")
      (node (ref "JP2") (pin "1") (pinfunction "1_1") (pintype "passive"))
      (node (ref "U$1") (pin "ROUT") (pinfunction "ROUT_ROUT") (pintype "output"))
    )
    (net (code "72") (name "TFT_A0{slash}DC") (class "Default")
      (node (ref "J5") (pin "8") (pinfunction "KL_8") (pintype "passive"))
      (node (ref "JP1") (pin "4") (pinfunction "4_4") (pintype "passive"))
      (node (ref "U$2") (pin "P$12") (pinfunction "A0_P$12") (pintype "bidirectional"))
    )
    (net (code "73") (name "TFT_CS") (class "Default")
      (node (ref "J10") (pin "9") (pinfunction "KL_9") (pintype "passive"))
      (node (ref "JP1") (pin "7") (pinfunction "7_7") (pintype "passive"))
      (node (ref "U$2") (pin "P$14") (pinfunction "CS_P$14") (pintype "bidirectional"))
    )
    (net (code "74") (name "TFT_RST") (class "Default")
      (node (ref "J5") (pin "3") (pinfunction "KL_3") (pintype "passive"))
      (node (ref "JP1") (pin "3") (pinfunction "3_3") (pintype "passive"))
      (node (ref "U$2") (pin "P$13") (pinfunction "RST_P$13") (pintype "bidirectional"))
    )
    (net (code "75") (name "TFT_SDA") (class "Default")
      (node (ref "J10") (pin "6") (pinfunction "KL_6") (pintype "passive"))
      (node (ref "JP1") (pin "5") (pinfunction "5_5") (pintype "passive"))
      (node (ref "U$2") (pin "P$11") (pinfunction "SDA_P$11") (pintype "bidirectional"))
    )
    (net (code "76") (name "unconnected-(IC1A-~{QH}-Pad7)") (class "Default")
      (node (ref "IC1") (pin "7") (pinfunction "~{QH}_7") (pintype "output"))
    )
    (net (code "77") (name "unconnected-(IC2A-QH*-Pad9)") (class "Default")
      (node (ref "IC2") (pin "9") (pinfunction "QH*_9") (pintype "tri_state"))
    )
    (net (code "78") (name "unconnected-(IC3A-SER-Pad10)") (class "Default")
      (node (ref "IC3") (pin "10") (pinfunction "SER_10") (pintype "input"))
    )
    (net (code "79") (name "unconnected-(IC3A-~{QH}-Pad7)") (class "Default")
      (node (ref "IC3") (pin "7") (pinfunction "~{QH}_7") (pintype "output"))
    )
    (net (code "80") (name "unconnected-(IC4A-~{QH}-Pad7)") (class "Default")
      (node (ref "IC4") (pin "7") (pinfunction "~{QH}_7") (pintype "output"))
    )
    (net (code "81") (name "unconnected-(IC5A-~{QH}-Pad7)") (class "Default")
      (node (ref "IC5") (pin "7") (pinfunction "~{QH}_7") (pintype "output"))
    )
    (net (code "82") (name "unconnected-(U$1-PadDEMP)") (class "Default")
      (node (ref "U$1") (pin "DEMP") (pinfunction "DEMP_DEMP") (pintype "input"))
    )
    (net (code "83") (name "unconnected-(U$1-PadSCK)") (class "Default")
      (node (ref "U$1") (pin "SCK") (pinfunction "SCK_SCK") (pintype "input"))
    )
    (net (code "84") (name "unconnected-(U$1-PadXSMT)") (class "Default")
      (node (ref "U$1") (pin "XSMT") (pinfunction "XSMT_XSMT") (pintype "input"))
    )
    (net (code "85") (name "unconnected-(U$2-SD_CS-PadP$6)") (class "Default")
      (node (ref "U$2") (pin "P$6") (pinfunction "SD_CS_P$6") (pintype "bidirectional"))
    )
    (net (code "86") (name "unconnected-(U$2-SD_MISO-PadP$4)") (class "Default")
      (node (ref "U$2") (pin "P$4") (pinfunction "SD_MISO_P$4") (pintype "bidirectional"))
    )
    (net (code "87") (name "unconnected-(U$2-SD_MOSI-PadP$5)") (class "Default")
      (node (ref "U$2") (pin "P$5") (pinfunction "SD_MOSI_P$5") (pintype "bidirectional"))
    )
    (net (code "88") (name "unconnected-(U$2-SD_SCK-PadP$3)") (class "Default")
      (node (ref "U$2") (pin "P$3") (pinfunction "SD_SCK_P$3") (pintype "bidirectional"))
    )
  )
)
